# heatbed.net
KiCad netlist of a schematic drawn in EAGLE
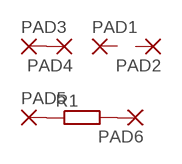
[diagram p0: schematic, sheet 1]

(export (version "E")
  (design (tool "Eeschema 10.0.6"))
  (components
    (comp (ref "PAD1")
      (value "SMD5")
      (footprint "eagle-import:SMD2,54-5,08")
      (libsource (lib "eagle-import") (part "SMD5"))
    )
    (comp (ref "PAD2")
      (value "SMD5")
      (footprint "eagle-import:SMD2,54-5,08")
      (libsource (lib "eagle-import") (part "SMD5"))
    )
    (comp (ref "PAD3")
      (value "SMD5")
      (footprint "eagle-import:SMD2,54-5,08")
      (libsource (lib "eagle-import") (part "SMD5"))
    )
    (comp (ref "PAD4")
      (value "SMD5")
      (footprint "eagle-import:SMD2,54-5,08")
      (libsource (lib "eagle-import") (part "SMD5"))
    )
    (comp (ref "PAD5")
      (value "SMD5")
      (footprint "eagle-import:SMD2,54-5,08")
      (libsource (lib "eagle-import") (part "SMD5"))
    )
    (comp (ref "PAD6")
      (value "SMD5")
      (footprint "eagle-import:SMD2,54-5,08")
      (libsource (lib "eagle-import") (part "SMD5"))
    )
    (comp (ref "R1")
      (value "R-EU_R0805")
      (footprint "eagle-import:R0805")
      (libsource (lib "eagle-import") (part "R-EU_R0805"))
    )
  )
  (nets
    (net (code "1") (name "Net-(PAD3-P)") (class "Default")
      (node (ref "PAD3") (pin "1") (pinfunction "P_1") (pintype "passive"))
      (node (ref "PAD4") (pin "1") (pinfunction "P_1") (pintype "passive"))
    )
    (net (code "2") (name "Net-(PAD5-P)") (class "Default")
      (node (ref "PAD5") (pin "1") (pinfunction "P_1") (pintype "passive"))
      (node (ref "R1") (pin "1") (pinfunction "1_1") (pintype "passive"))
    )
    (net (code "3") (name "Net-(PAD6-P)") (class "Default")
      (node (ref "PAD6") (pin "1") (pinfunction "P_1") (pintype "passive"))
      (node (ref "R1") (pin "2") (pinfunction "2_2") (pintype "passive"))
    )
    (net (code "4") (name "unconnected-(PAD1-P-Pad1)") (class "Default")
      (node (ref "PAD1") (pin "1") (pinfunction "P_1") (pintype "passive"))
    )
    (net (code "5") (name "unconnected-(PAD2-P-Pad1)") (class "Default")
      (node (ref "PAD2") (pin "1") (pinfunction "P_1") (pintype "passive"))
    )
  )
)
